# Power.net
KiCad netlist of a schematic drawn in Altium Designer
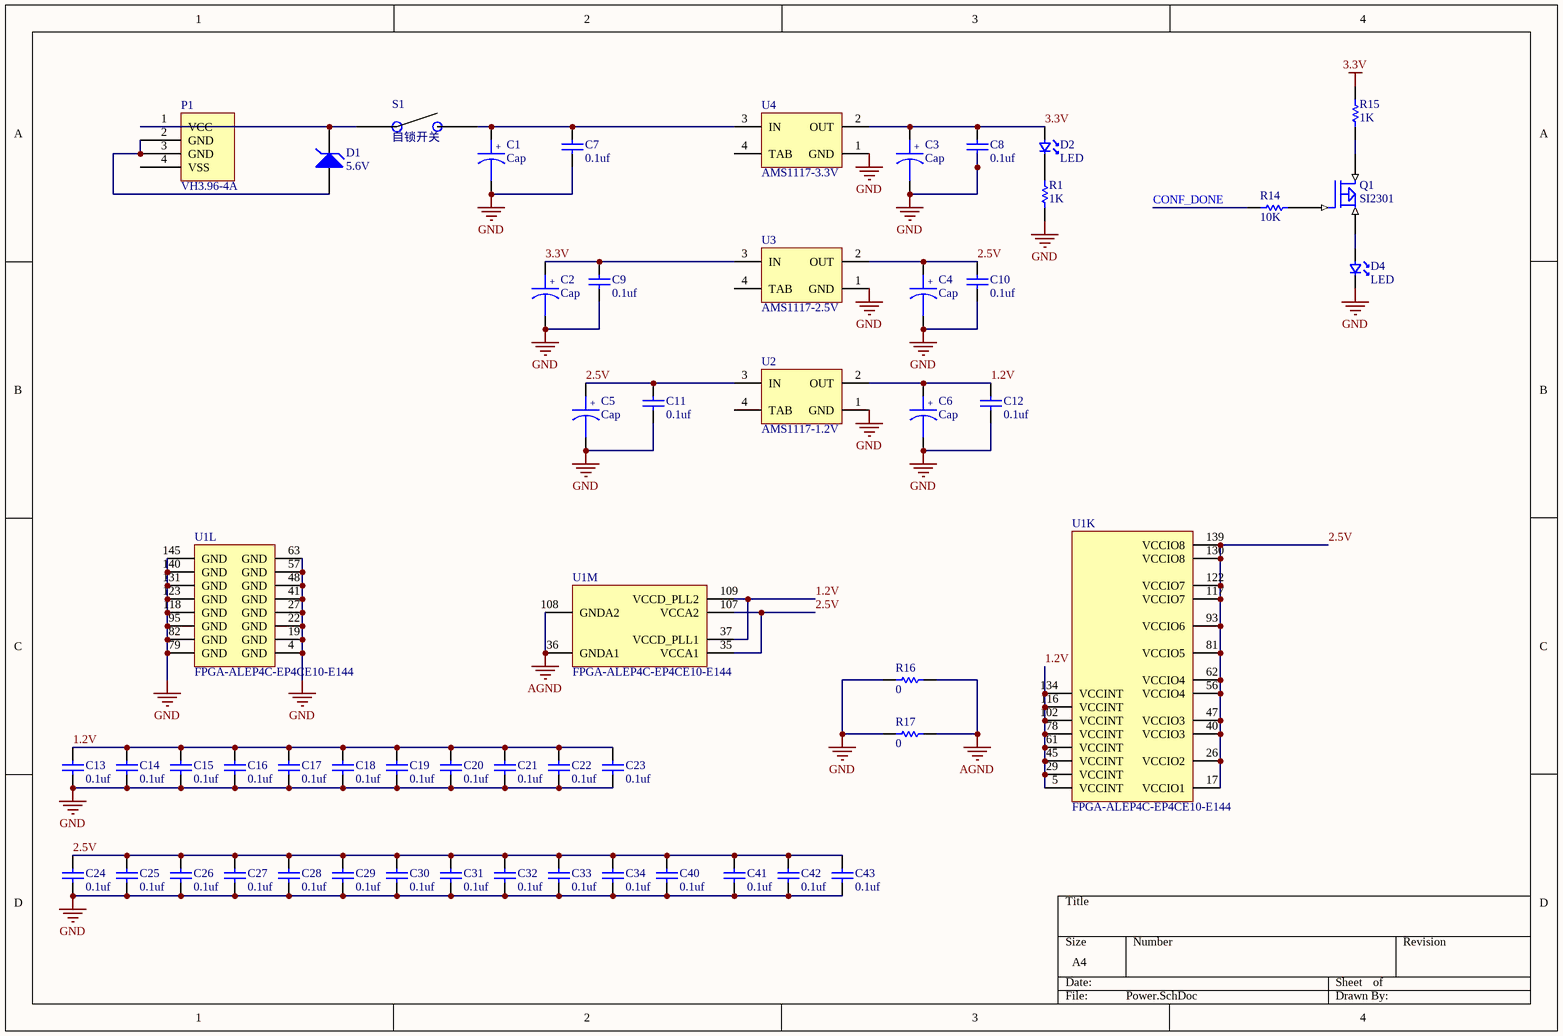
[diagram p0: Power.SchDoc]

(export (version "E")
  (design (tool "Eeschema 10.0.6"))
  (components
    (comp (ref "C1")
      (value "Cap")
      (footprint "7343-31 TYPE D")
      (libsource (lib "Schlib1") (part "Tantalium Cap"))
    )
    (comp (ref "C2")
      (value "Cap")
      (footprint "7343-31 TYPE D")
      (libsource (lib "Schlib1") (part "Tantalium Cap"))
    )
    (comp (ref "C3")
      (value "Cap")
      (footprint "7343-31 TYPE D")
      (libsource (lib "Schlib1") (part "Tantalium Cap"))
    )
    (comp (ref "C4")
      (value "Cap")
      (footprint "7343-31 TYPE D")
      (libsource (lib "Schlib1") (part "Tantalium Cap"))
    )
    (comp (ref "C5")
      (value "Cap")
      (footprint "7343-31 TYPE D")
      (libsource (lib "Schlib1") (part "Tantalium Cap"))
    )
    (comp (ref "C6")
      (value "Cap")
      (footprint "7343-31 TYPE D")
      (libsource (lib "Schlib1") (part "Tantalium Cap"))
    )
    (comp (ref "C7") (value "0.1uf") (footprint "0805") (libsource (lib "Schlib1") (part "Cap")))
    (comp (ref "C8") (value "0.1uf") (footprint "0805") (libsource (lib "Schlib1") (part "Cap")))
    (comp (ref "C9") (value "0.1uf") (footprint "0805") (libsource (lib "Schlib1") (part "Cap")))
    (comp (ref "C10") (value "0.1uf") (footprint "0805") (libsource (lib "Schlib1") (part "Cap")))
    (comp (ref "C11") (value "0.1uf") (footprint "0805") (libsource (lib "Schlib1") (part "Cap")))
    (comp (ref "C12") (value "0.1uf") (footprint "0805") (libsource (lib "Schlib1") (part "Cap")))
    (comp (ref "C13") (value "0.1uf") (footprint "0805") (libsource (lib "Schlib1") (part "Cap")))
    (comp (ref "C14") (value "0.1uf") (footprint "0805") (libsource (lib "Schlib1") (part "Cap")))
    (comp (ref "C15") (value "0.1uf") (footprint "0805") (libsource (lib "Schlib1") (part "Cap")))
    (comp (ref "C16") (value "0.1uf") (footprint "0805") (libsource (lib "Schlib1") (part "Cap")))
    (comp (ref "C17") (value "0.1uf") (footprint "0805") (libsource (lib "Schlib1") (part "Cap")))
    (comp (ref "C18") (value "0.1uf") (footprint "0805") (libsource (lib "Schlib1") (part "Cap")))
    (comp (ref "C19") (value "0.1uf") (footprint "0805") (libsource (lib "Schlib1") (part "Cap")))
    (comp (ref "C20") (value "0.1uf") (footprint "0805") (libsource (lib "Schlib1") (part "Cap")))
    (comp (ref "C21") (value "0.1uf") (footprint "0805") (libsource (lib "Schlib1") (part "Cap")))
    (comp (ref "C22") (value "0.1uf") (footprint "0805") (libsource (lib "Schlib1") (part "Cap")))
    (comp (ref "C23") (value "0.1uf") (footprint "0805") (libsource (lib "Schlib1") (part "Cap")))
    (comp (ref "C24") (value "0.1uf") (footprint "0805") (libsource (lib "Schlib1") (part "Cap")))
    (comp (ref "C25") (value "0.1uf") (footprint "0805") (libsource (lib "Schlib1") (part "Cap")))
    (comp (ref "C26") (value "0.1uf") (footprint "0805") (libsource (lib "Schlib1") (part "Cap")))
    (comp (ref "C27") (value "0.1uf") (footprint "0805") (libsource (lib "Schlib1") (part "Cap")))
    (comp (ref "C28") (value "0.1uf") (footprint "0805") (libsource (lib "Schlib1") (part "Cap")))
    (comp (ref "C29") (value "0.1uf") (footprint "0805") (libsource (lib "Schlib1") (part "Cap")))
    (comp (ref "C30") (value "0.1uf") (footprint "0805") (libsource (lib "Schlib1") (part "Cap")))
    (comp (ref "C31") (value "0.1uf") (footprint "0805") (libsource (lib "Schlib1") (part "Cap")))
    (comp (ref "C32") (value "0.1uf") (footprint "0805") (libsource (lib "Schlib1") (part "Cap")))
    (comp (ref "C33") (value "0.1uf") (footprint "0805") (libsource (lib "Schlib1") (part "Cap")))
    (comp (ref "C34") (value "0.1uf") (footprint "0805") (libsource (lib "Schlib1") (part "Cap")))
    (comp (ref "C40") (value "0.1uf") (footprint "0805") (libsource (lib "Schlib1") (part "Cap")))
    (comp (ref "C41") (value "0.1uf") (footprint "0805") (libsource (lib "Schlib1") (part "Cap")))
    (comp (ref "C42") (value "0.1uf") (footprint "0805") (libsource (lib "Schlib1") (part "Cap")))
    (comp (ref "C43") (value "0.1uf") (footprint "0805") (libsource (lib "Schlib1") (part "Cap")))
    (comp (ref "D1") (value "5.6V") (footprint "SMA/DO-214AC") (libsource (lib "Schlib1") (part "肖特基-5.6V")))
    (comp (ref "D2") (value "LED") (footprint "0805_s") (libsource (lib "Schlib1") (part "LED")))
    (comp (ref "D4") (value "LED") (footprint "0805_s") (libsource (lib "Schlib1") (part "LED")))
    (comp (ref "P1")
      (value "VH3.96-4A")
      (footprint "VH3.96-4P")
      (libsource (lib "Schlib1") (part "VH3.96-4A"))
    )
    (comp (ref "Q1") (value "SI2301") (footprint "SOT-23") (libsource (lib "Schlib1") (part "SI2301")))
    (comp (ref "R1") (value "1K") (footprint "0805") (libsource (lib "Schlib1") (part "Res")))
    (comp (ref "R14") (value "10K") (footprint "0805") (libsource (lib "Schlib1") (part "Res")))
    (comp (ref "R15") (value "1K") (footprint "0805") (libsource (lib "Schlib1") (part "Res")))
    (comp (ref "R16") (value "0") (footprint "0805") (libsource (lib "Schlib1") (part "Res")))
    (comp (ref "R17") (value "0") (footprint "0805") (libsource (lib "Schlib1") (part "Res")))
    (comp (ref "S1") (value "自锁开关") (footprint "AN88") (libsource (lib "Schlib1") (part "自锁开关")))
    (comp (ref "U1")
      (value "FPGA-ALEP4C-EP4CE10-E144")
      (footprint "EQFP144_A-165_D2-54_L")
      (libsource (lib "Schlib1") (part "FPGA-ALEP4C-EP4CE10-E144"))
    )
    (comp (ref "U2")
      (value "AMS1117-1.2V")
      (footprint "SOT223")
      (libsource (lib "Schlib1") (part "AMS1117-1.2V"))
    )
    (comp (ref "U3")
      (value "AMS1117-2.5V")
      (footprint "SOT223")
      (libsource (lib "Schlib1") (part "AMS1117-2.5V"))
    )
    (comp (ref "U4")
      (value "AMS1117-3.3V")
      (footprint "SOT223")
      (libsource (lib "Schlib1") (part "AMS1117-3.3V"))
    )
  )
  (nets
    (net (code "1") (name "/1.2V") (class "Default")
      (node (ref "C12") (pin "2") (pinfunction "2_2") (pintype "passive"))
      (node (ref "C13") (pin "2") (pinfunction "2_2") (pintype "passive"))
      (node (ref "C14") (pin "2") (pinfunction "2_2") (pintype "passive"))
      (node (ref "C15") (pin "2") (pinfunction "2_2") (pintype "passive"))
      (node (ref "C16") (pin "2") (pinfunction "2_2") (pintype "passive"))
      (node (ref "C17") (pin "2") (pinfunction "2_2") (pintype "passive"))
      (node (ref "C18") (pin "2") (pinfunction "2_2") (pintype "passive"))
      (node (ref "C19") (pin "2") (pinfunction "2_2") (pintype "passive"))
      (node (ref "C20") (pin "2") (pinfunction "2_2") (pintype "passive"))
      (node (ref "C21") (pin "2") (pinfunction "2_2") (pintype "passive"))
      (node (ref "C22") (pin "2") (pinfunction "2_2") (pintype "passive"))
      (node (ref "C23") (pin "2") (pinfunction "2_2") (pintype "passive"))
      (node (ref "C6") (pin "1") (pinfunction "1_1") (pintype "passive"))
      (node (ref "U1") (pin "102") (pinfunction "VCCINT_102") (pintype "power_in"))
      (node (ref "U1") (pin "109") (pinfunction "VCCD_PLL2_109") (pintype "power_in"))
      (node (ref "U1") (pin "116") (pinfunction "VCCINT_116") (pintype "power_in"))
      (node (ref "U1") (pin "134") (pinfunction "VCCINT_134") (pintype "power_in"))
      (node (ref "U1") (pin "29") (pinfunction "VCCINT_29") (pintype "power_in"))
      (node (ref "U1") (pin "37") (pinfunction "VCCD_PLL1_37") (pintype "power_in"))
      (node (ref "U1") (pin "45") (pinfunction "VCCINT_45") (pintype "power_in"))
      (node (ref "U1") (pin "5") (pinfunction "VCCINT_5") (pintype "power_in"))
      (node (ref "U1") (pin "61") (pinfunction "VCCINT_61") (pintype "power_in"))
      (node (ref "U1") (pin "78") (pinfunction "VCCINT_78") (pintype "power_in"))
      (node (ref "U2") (pin "2") (pinfunction "OUT_2") (pintype "power_in"))
    )
    (net (code "2") (name "/2.5V") (class "Default")
      (node (ref "C10") (pin "2") (pinfunction "2_2") (pintype "passive"))
      (node (ref "C11") (pin "2") (pinfunction "2_2") (pintype "passive"))
      (node (ref "C24") (pin "2") (pinfunction "2_2") (pintype "passive"))
      (node (ref "C25") (pin "2") (pinfunction "2_2") (pintype "passive"))
      (node (ref "C26") (pin "2") (pinfunction "2_2") (pintype "passive"))
      (node (ref "C27") (pin "2") (pinfunction "2_2") (pintype "passive"))
      (node (ref "C28") (pin "2") (pinfunction "2_2") (pintype "passive"))
      (node (ref "C29") (pin "2") (pinfunction "2_2") (pintype "passive"))
      (node (ref "C30") (pin "2") (pinfunction "2_2") (pintype "passive"))
      (node (ref "C31") (pin "2") (pinfunction "2_2") (pintype "passive"))
      (node (ref "C32") (pin "2") (pinfunction "2_2") (pintype "passive"))
      (node (ref "C33") (pin "2") (pinfunction "2_2") (pintype "passive"))
      (node (ref "C34") (pin "2") (pinfunction "2_2") (pintype "passive"))
      (node (ref "C4") (pin "1") (pinfunction "1_1") (pintype "passive"))
      (node (ref "C40") (pin "2") (pinfunction "2_2") (pintype "passive"))
      (node (ref "C41") (pin "2") (pinfunction "2_2") (pintype "passive"))
      (node (ref "C42") (pin "2") (pinfunction "2_2") (pintype "passive"))
      (node (ref "C43") (pin "2") (pinfunction "2_2") (pintype "passive"))
      (node (ref "C5") (pin "1") (pinfunction "1_1") (pintype "passive"))
      (node (ref "U1") (pin "107") (pinfunction "VCCA2_107") (pintype "power_in"))
      (node (ref "U1") (pin "117") (pinfunction "VCCIO7_117") (pintype "power_in"))
      (node (ref "U1") (pin "122") (pinfunction "VCCIO7_122") (pintype "power_in"))
      (node (ref "U1") (pin "130") (pinfunction "VCCIO8_130") (pintype "power_in"))
      (node (ref "U1") (pin "139") (pinfunction "VCCIO8_139") (pintype "power_in"))
      (node (ref "U1") (pin "17") (pinfunction "VCCIO1_17") (pintype "power_in"))
      (node (ref "U1") (pin "26") (pinfunction "VCCIO2_26") (pintype "power_in"))
      (node (ref "U1") (pin "35") (pinfunction "VCCA1_35") (pintype "power_in"))
      (node (ref "U1") (pin "40") (pinfunction "VCCIO3_40") (pintype "power_in"))
      (node (ref "U1") (pin "47") (pinfunction "VCCIO3_47") (pintype "power_in"))
      (node (ref "U1") (pin "56") (pinfunction "VCCIO4_56") (pintype "power_in"))
      (node (ref "U1") (pin "62") (pinfunction "VCCIO4_62") (pintype "power_in"))
      (node (ref "U1") (pin "81") (pinfunction "VCCIO5_81") (pintype "power_in"))
      (node (ref "U1") (pin "93") (pinfunction "VCCIO6_93") (pintype "power_in"))
      (node (ref "U2") (pin "3") (pinfunction "IN_3") (pintype "power_in"))
      (node (ref "U3") (pin "2") (pinfunction "OUT_2") (pintype "power_in"))
    )
    (net (code "3") (name "/CONF_DONE") (class "Default")
      (node (ref "R14") (pin "1") (pinfunction "1_1") (pintype "passive"))
    )
    (net (code "4") (name "3.3V") (class "Default")
      (node (ref "C2") (pin "1") (pinfunction "1_1") (pintype "passive"))
      (node (ref "C3") (pin "1") (pinfunction "1_1") (pintype "passive"))
      (node (ref "C8") (pin "2") (pinfunction "2_2") (pintype "passive"))
      (node (ref "C9") (pin "2") (pinfunction "2_2") (pintype "passive"))
      (node (ref "D2") (pin "2") (pinfunction "2_2") (pintype "passive"))
      (node (ref "R15") (pin "2") (pinfunction "2_2") (pintype "passive"))
      (node (ref "U3") (pin "3") (pinfunction "IN_3") (pintype "power_in"))
      (node (ref "U4") (pin "2") (pinfunction "OUT_2") (pintype "power_in"))
    )
    (net (code "5") (name "AGND") (class "Default")
      (node (ref "R16") (pin "2") (pinfunction "2_2") (pintype "passive"))
      (node (ref "R17") (pin "2") (pinfunction "2_2") (pintype "passive"))
      (node (ref "U1") (pin "108") (pinfunction "GNDA2_108") (pintype "power_in"))
      (node (ref "U1") (pin "36") (pinfunction "GNDA1_36") (pintype "power_in"))
    )
    (net (code "6") (name "GND") (class "Default")
      (node (ref "C1") (pin "2") (pinfunction "2_2") (pintype "passive"))
      (node (ref "C10") (pin "1") (pinfunction "1_1") (pintype "passive"))
      (node (ref "C11") (pin "1") (pinfunction "1_1") (pintype "passive"))
      (node (ref "C12") (pin "1") (pinfunction "1_1") (pintype "passive"))
      (node (ref "C13") (pin "1") (pinfunction "1_1") (pintype "passive"))
      (node (ref "C14") (pin "1") (pinfunction "1_1") (pintype "passive"))
      (node (ref "C15") (pin "1") (pinfunction "1_1") (pintype "passive"))
      (node (ref "C16") (pin "1") (pinfunction "1_1") (pintype "passive"))
      (node (ref "C17") (pin "1") (pinfunction "1_1") (pintype "passive"))
      (node (ref "C18") (pin "1") (pinfunction "1_1") (pintype "passive"))
      (node (ref "C19") (pin "1") (pinfunction "1_1") (pintype "passive"))
      (node (ref "C2") (pin "2") (pinfunction "2_2") (pintype "passive"))
      (node (ref "C20") (pin "1") (pinfunction "1_1") (pintype "passive"))
      (node (ref "C21") (pin "1") (pinfunction "1_1") (pintype "passive"))
      (node (ref "C22") (pin "1") (pinfunction "1_1") (pintype "passive"))
      (node (ref "C23") (pin "1") (pinfunction "1_1") (pintype "passive"))
      (node (ref "C24") (pin "1") (pinfunction "1_1") (pintype "passive"))
      (node (ref "C25") (pin "1") (pinfunction "1_1") (pintype "passive"))
      (node (ref "C26") (pin "1") (pinfunction "1_1") (pintype "passive"))
      (node (ref "C27") (pin "1") (pinfunction "1_1") (pintype "passive"))
      (node (ref "C28") (pin "1") (pinfunction "1_1") (pintype "passive"))
      (node (ref "C29") (pin "1") (pinfunction "1_1") (pintype "passive"))
      (node (ref "C3") (pin "2") (pinfunction "2_2") (pintype "passive"))
      (node (ref "C30") (pin "1") (pinfunction "1_1") (pintype "passive"))
      (node (ref "C31") (pin "1") (pinfunction "1_1") (pintype "passive"))
      (node (ref "C32") (pin "1") (pinfunction "1_1") (pintype "passive"))
      (node (ref "C33") (pin "1") (pinfunction "1_1") (pintype "passive"))
      (node (ref "C34") (pin "1") (pinfunction "1_1") (pintype "passive"))
      (node (ref "C4") (pin "2") (pinfunction "2_2") (pintype "passive"))
      (node (ref "C40") (pin "1") (pinfunction "1_1") (pintype "passive"))
      (node (ref "C41") (pin "1") (pinfunction "1_1") (pintype "passive"))
      (node (ref "C42") (pin "1") (pinfunction "1_1") (pintype "passive"))
      (node (ref "C43") (pin "1") (pinfunction "1_1") (pintype "passive"))
      (node (ref "C5") (pin "2") (pinfunction "2_2") (pintype "passive"))
      (node (ref "C6") (pin "2") (pinfunction "2_2") (pintype "passive"))
      (node (ref "C7") (pin "1") (pinfunction "1_1") (pintype "passive"))
      (node (ref "C8") (pin "1") (pinfunction "1_1") (pintype "passive"))
      (node (ref "C9") (pin "1") (pinfunction "1_1") (pintype "passive"))
      (node (ref "D4") (pin "1") (pinfunction "1_1") (pintype "passive"))
      (node (ref "R1") (pin "1") (pinfunction "1_1") (pintype "passive"))
      (node (ref "R16") (pin "1") (pinfunction "1_1") (pintype "passive"))
      (node (ref "R17") (pin "1") (pinfunction "1_1") (pintype "passive"))
      (node (ref "U1") (pin "118") (pinfunction "GND_118") (pintype "power_in"))
      (node (ref "U1") (pin "123") (pinfunction "GND_123") (pintype "power_in"))
      (node (ref "U1") (pin "131") (pinfunction "GND_131") (pintype "power_in"))
      (node (ref "U1") (pin "140") (pinfunction "GND_140") (pintype "power_in"))
      (node (ref "U1") (pin "145") (pinfunction "GND_145") (pintype "power_in"))
      (node (ref "U1") (pin "19") (pinfunction "GND_19") (pintype "power_in"))
      (node (ref "U1") (pin "22") (pinfunction "GND_22") (pintype "power_in"))
      (node (ref "U1") (pin "27") (pinfunction "GND_27") (pintype "power_in"))
      (node (ref "U1") (pin "4") (pinfunction "GND_4") (pintype "power_in"))
      (node (ref "U1") (pin "41") (pinfunction "GND_41") (pintype "power_in"))
      (node (ref "U1") (pin "48") (pinfunction "GND_48") (pintype "power_in"))
      (node (ref "U1") (pin "57") (pinfunction "GND_57") (pintype "power_in"))
      (node (ref "U1") (pin "63") (pinfunction "GND_63") (pintype "power_in"))
      (node (ref "U1") (pin "79") (pinfunction "GND_79") (pintype "power_in"))
      (node (ref "U1") (pin "82") (pinfunction "GND_82") (pintype "power_in"))
      (node (ref "U1") (pin "95") (pinfunction "GND_95") (pintype "power_in"))
      (node (ref "U2") (pin "1") (pinfunction "GND_1") (pintype "power_in"))
      (node (ref "U3") (pin "1") (pinfunction "GND_1") (pintype "power_in"))
      (node (ref "U4") (pin "1") (pinfunction "GND_1") (pintype "power_in"))
    )
    (net (code "7") (name "Net-(D1-A)") (class "Default")
      (node (ref "D1") (pin "1") (pinfunction "A_1") (pintype "passive"))
      (node (ref "P1") (pin "2") (pinfunction "GND_2") (pintype "passive"))
      (node (ref "P1") (pin "3") (pinfunction "GND_3") (pintype "passive"))
    )
    (net (code "8") (name "Net-(D1-K)") (class "Default")
      (node (ref "D1") (pin "2") (pinfunction "K_2") (pintype "passive"))
      (node (ref "P1") (pin "1") (pinfunction "VCC_1") (pintype "passive"))
      (node (ref "S1") (pin "4") (pinfunction "4_4") (pintype "passive"))
    )
    (net (code "9") (name "Net-(D2-Pad1)") (class "Default")
      (node (ref "D2") (pin "1") (pinfunction "1_1") (pintype "passive"))
      (node (ref "R1") (pin "2") (pinfunction "2_2") (pintype "passive"))
    )
    (net (code "10") (name "Net-(Q1-D)") (class "Default")
      (node (ref "D4") (pin "2") (pinfunction "2_2") (pintype "passive"))
      (node (ref "Q1") (pin "3") (pinfunction "D_3") (pintype "input"))
    )
    (net (code "11") (name "Net-(Q1-G)") (class "Default")
      (node (ref "Q1") (pin "1") (pinfunction "G_1") (pintype "input"))
      (node (ref "R14") (pin "2") (pinfunction "2_2") (pintype "passive"))
    )
    (net (code "12") (name "Net-(Q1-S)") (class "Default")
      (node (ref "Q1") (pin "2") (pinfunction "S_2") (pintype "input"))
      (node (ref "R15") (pin "1") (pinfunction "1_1") (pintype "passive"))
    )
    (net (code "13") (name "Net-(U4-IN)") (class "Default")
      (node (ref "C1") (pin "1") (pinfunction "1_1") (pintype "passive"))
      (node (ref "C7") (pin "2") (pinfunction "2_2") (pintype "passive"))
      (node (ref "S1") (pin "6") (pinfunction "6_6") (pintype "passive"))
      (node (ref "U4") (pin "3") (pinfunction "IN_3") (pintype "power_in"))
    )
    (net (code "14") (name "unconnected-(P1-VSS-Pad4)") (class "Default")
      (node (ref "P1") (pin "4") (pinfunction "VSS_4") (pintype "passive"))
    )
    (net (code "15") (name "unconnected-(U2-TAB-Pad4)") (class "Default")
      (node (ref "U2") (pin "4") (pinfunction "TAB_4") (pintype "power_in"))
    )
    (net (code "16") (name "unconnected-(U3-TAB-Pad4)") (class "Default")
      (node (ref "U3") (pin "4") (pinfunction "TAB_4") (pintype "power_in"))
    )
    (net (code "17") (name "unconnected-(U4-TAB-Pad4)") (class "Default")
      (node (ref "U4") (pin "4") (pinfunction "TAB_4") (pintype "power_in"))
    )
  )
)
